# fish-1_0.net
KiCad netlist of a schematic drawn in EAGLE
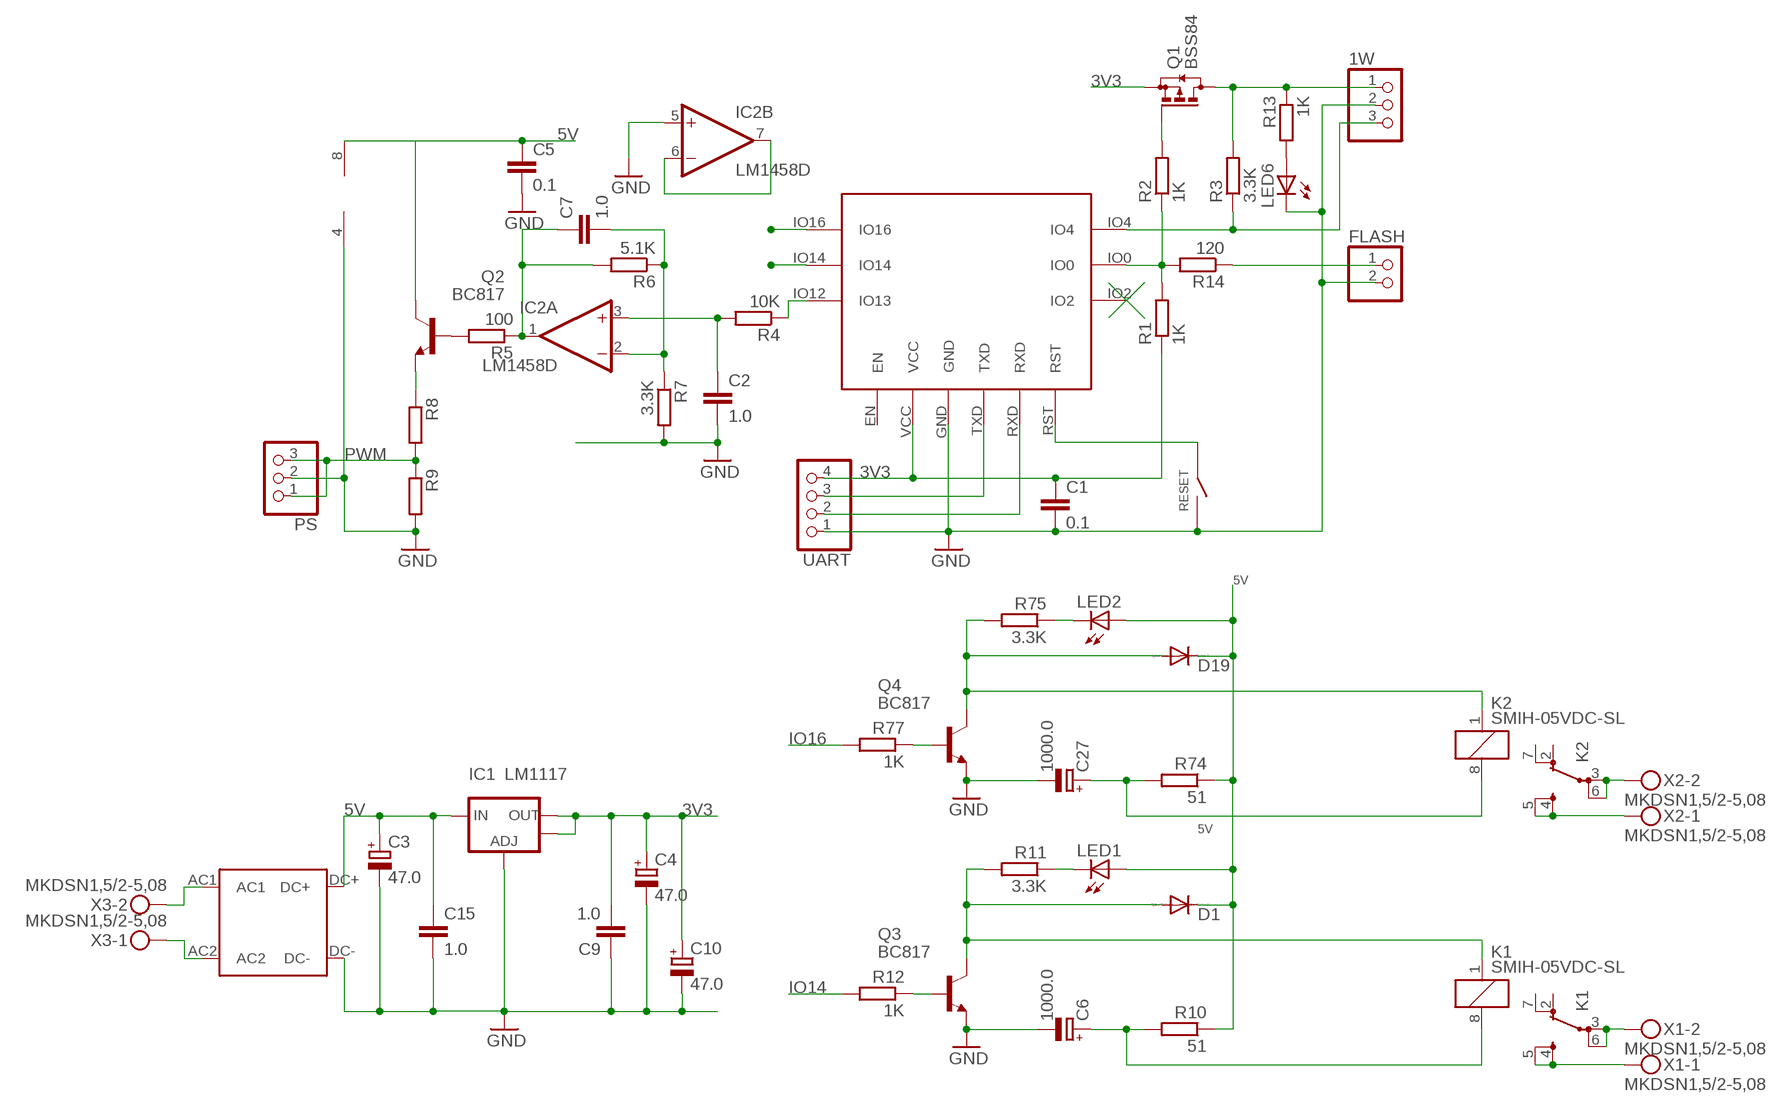
[diagram p0: schematic, sheet 1]

(export (version "E")
  (design (tool "Eeschema 10.0.6"))
  (components
    (comp (ref "1W")
      (value "PINHD-1X3/90")
      (footprint "eagle-import:1X03_90")
      (libsource (lib "eagle-import") (part "PINHD-1X3/90"))
    )
    (comp (ref "C1")
      (value "0.1")
      (footprint "eagle-import:C0805")
      (libsource (lib "eagle-import") (part "C-EUC0805"))
    )
    (comp (ref "C2")
      (value "1.0")
      (footprint "eagle-import:C0805")
      (libsource (lib "eagle-import") (part "C-EUC0805"))
    )
    (comp (ref "C3")
      (value "47.0")
      (footprint "eagle-import:SMC_D")
      (libsource (lib "eagle-import") (part "CPOL-EUSMCD"))
    )
    (comp (ref "C4")
      (value "47.0")
      (footprint "eagle-import:SMC_B")
      (libsource (lib "eagle-import") (part "CPOL-EUSMCB"))
    )
    (comp (ref "C5")
      (value "0.1")
      (footprint "eagle-import:C0805")
      (libsource (lib "eagle-import") (part "C-EUC0805"))
    )
    (comp (ref "C6")
      (value "1000.0")
      (footprint "eagle-import:E3,5-8")
      (libsource (lib "eagle-import") (part "CPOL-EUE3.5-8"))
    )
    (comp (ref "C7")
      (value "1.0")
      (footprint "eagle-import:C0805")
      (libsource (lib "eagle-import") (part "C-EUC0805"))
    )
    (comp (ref "C9")
      (value "1.0")
      (footprint "eagle-import:C0805")
      (libsource (lib "eagle-import") (part "C-EUC0805"))
    )
    (comp (ref "C10")
      (value "47.0")
      (footprint "eagle-import:SMC_D")
      (libsource (lib "eagle-import") (part "CPOL-EUSMCD"))
    )
    (comp (ref "C15")
      (value "1.0")
      (footprint "eagle-import:C0805")
      (libsource (lib "eagle-import") (part "C-EUC0805"))
    )
    (comp (ref "C27")
      (value "1000.0")
      (footprint "eagle-import:E3,5-8")
      (libsource (lib "eagle-import") (part "CPOL-EUE3.5-8"))
    )
    (comp (ref "D1")
      (value "DIODE-SOD123")
      (footprint "eagle-import:SOD123")
      (libsource (lib "eagle-import") (part "DIODE-SOD123"))
    )
    (comp (ref "D19")
      (value "DIODE-SOD123")
      (footprint "eagle-import:SOD123")
      (libsource (lib "eagle-import") (part "DIODE-SOD123"))
    )
    (comp (ref "ESP-M3")
      (value "ESP-M3")
      (footprint "eagle-import:ESP-M3")
      (libsource (lib "eagle-import") (part "ESP-M3"))
    )
    (comp (ref "FLASH")
      (value "PINHD-1X2/90")
      (footprint "eagle-import:1X02_90")
      (libsource (lib "eagle-import") (part "PINHD-1X2/90"))
    )
    (comp (ref "IC1")
      (value "LM1117")
      (footprint "eagle-import:SOT223")
      (libsource (lib "eagle-import") (part "V_REG_LM1117SOT223"))
    )
    (comp (ref "IC2")
      (value "LM1458D")
      (footprint "eagle-import:SO08")
      (libsource (lib "eagle-import") (part "1458DLM"))
    )
    (comp (ref "K1")
      (value "SMIH-05VDC-SL")
      (footprint "eagle-import:FTR-K1C")
      (libsource (lib "eagle-import") (part "FTR-K1C"))
    )
    (comp (ref "K2")
      (value "SMIH-05VDC-SL")
      (footprint "eagle-import:FTR-K1C")
      (libsource (lib "eagle-import") (part "FTR-K1C"))
    )
    (comp (ref "LED1")
      (value "LEDSMT1206")
      (footprint "eagle-import:1206")
      (libsource (lib "eagle-import") (part "LEDSMT1206"))
    )
    (comp (ref "LED2")
      (value "LEDSMT1206")
      (footprint "eagle-import:1206")
      (libsource (lib "eagle-import") (part "LEDSMT1206"))
    )
    (comp (ref "LED6")
      (value "LEDSMT1206")
      (footprint "eagle-import:1206")
      (libsource (lib "eagle-import") (part "LEDSMT1206"))
    )
    (comp (ref "PS")
      (value "PINHD-1X3/90")
      (footprint "eagle-import:1X03_90")
      (libsource (lib "eagle-import") (part "PINHD-1X3/90"))
    )
    (comp (ref "Q1")
      (value "BSS84")
      (footprint "eagle-import:SOT23")
      (libsource (lib "eagle-import") (part "BSS84"))
    )
    (comp (ref "Q2")
      (value "BC817")
      (footprint "eagle-import:SOT23-BEC")
      (libsource (lib "eagle-import") (part "BC817SMD-40"))
    )
    (comp (ref "Q3")
      (value "BC817")
      (footprint "eagle-import:SOT23-BEC")
      (libsource (lib "eagle-import") (part "BC817SMD-40"))
    )
    (comp (ref "Q4")
      (value "BC817")
      (footprint "eagle-import:SOT23-BEC")
      (libsource (lib "eagle-import") (part "BC817SMD-40"))
    )
    (comp (ref "R1")
      (value "1K")
      (footprint "eagle-import:R0603")
      (libsource (lib "eagle-import") (part "R-EU_R0603"))
    )
    (comp (ref "R2")
      (value "1K")
      (footprint "eagle-import:R0603")
      (libsource (lib "eagle-import") (part "R-EU_R0603"))
    )
    (comp (ref "R3")
      (value "3.3K")
      (footprint "eagle-import:R0603")
      (libsource (lib "eagle-import") (part "R-EU_R0603"))
    )
    (comp (ref "R4")
      (value "10K")
      (footprint "eagle-import:R0603")
      (libsource (lib "eagle-import") (part "R-EU_R0603"))
    )
    (comp (ref "R5")
      (value "100")
      (footprint "eagle-import:R0603")
      (libsource (lib "eagle-import") (part "R-EU_R0603"))
    )
    (comp (ref "R6")
      (value "5.1K")
      (footprint "eagle-import:R0603")
      (libsource (lib "eagle-import") (part "R-EU_R0603"))
    )
    (comp (ref "R7")
      (value "3.3K")
      (footprint "eagle-import:R0603")
      (libsource (lib "eagle-import") (part "R-EU_R0603"))
    )
    (comp (ref "R8")
      (value "R-EU_R0603")
      (footprint "eagle-import:R0603")
      (libsource (lib "eagle-import") (part "R-EU_R0603"))
    )
    (comp (ref "R9")
      (value "R-EU_R0603")
      (footprint "eagle-import:R0603")
      (libsource (lib "eagle-import") (part "R-EU_R0603"))
    )
    (comp (ref "R10")
      (value "51")
      (footprint "eagle-import:R1206")
      (libsource (lib "eagle-import") (part "R-EU_R1206"))
    )
    (comp (ref "R11")
      (value "3.3K")
      (footprint "eagle-import:R0603")
      (libsource (lib "eagle-import") (part "R-EU_R0603"))
    )
    (comp (ref "R12")
      (value "1K")
      (footprint "eagle-import:R0603")
      (libsource (lib "eagle-import") (part "R-EU_R0603"))
    )
    (comp (ref "R13")
      (value "1K")
      (footprint "eagle-import:R0603")
      (libsource (lib "eagle-import") (part "R-EU_R0603"))
    )
    (comp (ref "R14")
      (value "120")
      (footprint "eagle-import:R0603")
      (libsource (lib "eagle-import") (part "R-EU_R0603"))
    )
    (comp (ref "R74")
      (value "51")
      (footprint "eagle-import:R1206")
      (libsource (lib "eagle-import") (part "R-EU_R1206"))
    )
    (comp (ref "R75")
      (value "3.3K")
      (footprint "eagle-import:R0603")
      (libsource (lib "eagle-import") (part "R-EU_R0603"))
    )
    (comp (ref "R77")
      (value "1K")
      (footprint "eagle-import:R0603")
      (libsource (lib "eagle-import") (part "R-EU_R0603"))
    )
    (comp (ref "RESET")
      (value "TACT3X4")
      (footprint "eagle-import:TACT3X4")
      (libsource (lib "eagle-import") (part "TACT3X4"))
    )
    (comp (ref "U$1")
      (value "AC-DC/10W-12V")
      (footprint "eagle-import:AC-DC_10W")
      (libsource (lib "eagle-import") (part "AC-DC/10W-12V"))
    )
    (comp (ref "UART")
      (value "PINHD-1X4/90")
      (footprint "eagle-import:1X04_90")
      (libsource (lib "eagle-import") (part "PINHD-1X4/90"))
    )
    (comp (ref "X1")
      (value "MKDSN1,5/2-5,08")
      (footprint "eagle-import:MKDSN1,5_2-5,08")
      (libsource (lib "eagle-import") (part "MKDSN1,5/2-5,08"))
    )
    (comp (ref "X2")
      (value "MKDSN1,5/2-5,08")
      (footprint "eagle-import:MKDSN1,5_2-5,08")
      (libsource (lib "eagle-import") (part "MKDSN1,5/2-5,08"))
    )
    (comp (ref "X3")
      (value "MKDSN1,5/2-5,08")
      (footprint "eagle-import:MKDSN1,5_2-5,08")
      (libsource (lib "eagle-import") (part "MKDSN1,5/2-5,08"))
    )
  )
  (nets
    (net (code "1") (name "/3V3") (class "Default")
      (node (ref "C1") (pin "1") (pinfunction "1_1") (pintype "passive"))
      (node (ref "C10") (pin "+") (pinfunction "+_+") (pintype "passive"))
      (node (ref "C4") (pin "+") (pinfunction "+_+") (pintype "passive"))
      (node (ref "C9") (pin "2") (pinfunction "2_2") (pintype "passive"))
      (node (ref "ESP-M3") (pin "VCC") (pinfunction "VCC_VCC") (pintype "bidirectional"))
      (node (ref "IC1") (pin "2") (pinfunction "OUT_2") (pintype "output"))
      (node (ref "IC1") (pin "4") (pinfunction "OUT_4") (pintype "output"))
      (node (ref "Q1") (pin "2") (pinfunction "S_2") (pintype "passive"))
      (node (ref "R1") (pin "1") (pinfunction "1_1") (pintype "passive"))
      (node (ref "UART") (pin "4") (pinfunction "4_4") (pintype "passive"))
    )
    (net (code "2") (name "/5V") (class "Default")
      (node (ref "C15") (pin "1") (pinfunction "1_1") (pintype "passive"))
      (node (ref "C3") (pin "+") (pinfunction "+_+") (pintype "passive"))
      (node (ref "C5") (pin "1") (pinfunction "1_1") (pintype "passive"))
      (node (ref "D1") (pin "C") (pinfunction "C_C") (pintype "passive"))
      (node (ref "D19") (pin "C") (pinfunction "C_C") (pintype "passive"))
      (node (ref "IC1") (pin "3") (pinfunction "IN_3") (pintype "input"))
      (node (ref "IC2") (pin "8") (pinfunction "V+_8") (pintype "power_in"))
      (node (ref "LED1") (pin "A") (pinfunction "A_A") (pintype "passive"))
      (node (ref "LED2") (pin "A") (pinfunction "A_A") (pintype "passive"))
      (node (ref "Q2") (pin "C") (pinfunction "C_C") (pintype "passive"))
      (node (ref "R10") (pin "1") (pinfunction "1_1") (pintype "passive"))
      (node (ref "R74") (pin "1") (pinfunction "1_1") (pintype "passive"))
      (node (ref "U$1") (pin "DC+") (pinfunction "DC+_DC+") (pintype "power_in"))
    )
    (net (code "3") (name "/IO14") (class "Default")
      (node (ref "ESP-M3") (pin "IO14") (pinfunction "IO14_IO14") (pintype "bidirectional"))
      (node (ref "R12") (pin "2") (pinfunction "2_2") (pintype "passive"))
    )
    (net (code "4") (name "/IO16") (class "Default")
      (node (ref "ESP-M3") (pin "IO16") (pinfunction "IO16_IO16") (pintype "bidirectional"))
      (node (ref "R77") (pin "2") (pinfunction "2_2") (pintype "passive"))
    )
    (net (code "5") (name "/PWM") (class "Default")
      (node (ref "PS") (pin "1") (pinfunction "1_1") (pintype "passive"))
      (node (ref "PS") (pin "3") (pinfunction "3_3") (pintype "passive"))
      (node (ref "R8") (pin "2") (pinfunction "2_2") (pintype "passive"))
      (node (ref "R9") (pin "1") (pinfunction "1_1") (pintype "passive"))
    )
    (net (code "6") (name "GND") (class "Default")
      (node (ref "1W") (pin "2") (pinfunction "2_2") (pintype "passive"))
      (node (ref "C1") (pin "2") (pinfunction "2_2") (pintype "passive"))
      (node (ref "C10") (pin "-") (pinfunction "-_-") (pintype "passive"))
      (node (ref "C15") (pin "2") (pinfunction "2_2") (pintype "passive"))
      (node (ref "C2") (pin "2") (pinfunction "2_2") (pintype "passive"))
      (node (ref "C27") (pin "-") (pinfunction "-_-") (pintype "passive"))
      (node (ref "C3") (pin "-") (pinfunction "-_-") (pintype "passive"))
      (node (ref "C4") (pin "-") (pinfunction "-_-") (pintype "passive"))
      (node (ref "C5") (pin "2") (pinfunction "2_2") (pintype "passive"))
      (node (ref "C6") (pin "-") (pinfunction "-_-") (pintype "passive"))
      (node (ref "C9") (pin "1") (pinfunction "1_1") (pintype "passive"))
      (node (ref "ESP-M3") (pin "GND") (pinfunction "GND_GND") (pintype "bidirectional"))
      (node (ref "FLASH") (pin "2") (pinfunction "2_2") (pintype "passive"))
      (node (ref "IC1") (pin "1") (pinfunction "ADJ_1") (pintype "input"))
      (node (ref "IC2") (pin "4") (pinfunction "V-_4") (pintype "power_in"))
      (node (ref "IC2") (pin "5") (pinfunction "+IN_5") (pintype "input"))
      (node (ref "LED6") (pin "C") (pinfunction "C_C") (pintype "passive"))
      (node (ref "PS") (pin "2") (pinfunction "2_2") (pintype "passive"))
      (node (ref "Q3") (pin "E") (pinfunction "E_E") (pintype "passive"))
      (node (ref "Q4") (pin "E") (pinfunction "E_E") (pintype "passive"))
      (node (ref "R7") (pin "2") (pinfunction "2_2") (pintype "passive"))
      (node (ref "R9") (pin "2") (pinfunction "2_2") (pintype "passive"))
      (node (ref "RESET") (pin "P$2") (pinfunction "P$2_P$2") (pintype "bidirectional"))
      (node (ref "U$1") (pin "DC-") (pinfunction "DC-_DC-") (pintype "power_in"))
      (node (ref "UART") (pin "1") (pinfunction "1_1") (pintype "passive"))
    )
    (net (code "7") (name "Net-(1W-Pad3)") (class "Default")
      (node (ref "1W") (pin "3") (pinfunction "3_3") (pintype "passive"))
      (node (ref "ESP-M3") (pin "IO4") (pinfunction "IO4_IO4") (pintype "bidirectional"))
      (node (ref "R3") (pin "1") (pinfunction "1_1") (pintype "passive"))
    )
    (net (code "8") (name "Net-(D1-PadA)") (class "Default")
      (node (ref "D1") (pin "A") (pinfunction "A_A") (pintype "passive"))
      (node (ref "K1") (pin "1") (pinfunction "1_1") (pintype "passive"))
      (node (ref "Q3") (pin "C") (pinfunction "C_C") (pintype "passive"))
      (node (ref "R11") (pin "2") (pinfunction "2_2") (pintype "passive"))
    )
    (net (code "9") (name "Net-(D19-PadA)") (class "Default")
      (node (ref "D19") (pin "A") (pinfunction "A_A") (pintype "passive"))
      (node (ref "K2") (pin "1") (pinfunction "1_1") (pintype "passive"))
      (node (ref "Q4") (pin "C") (pinfunction "C_C") (pintype "passive"))
      (node (ref "R75") (pin "2") (pinfunction "2_2") (pintype "passive"))
    )
    (net (code "10") (name "Net-(ESP-M3-IO13)") (class "Default")
      (node (ref "ESP-M3") (pin "IO12") (pinfunction "IO13_IO12") (pintype "bidirectional"))
      (node (ref "R4") (pin "1") (pinfunction "1_1") (pintype "passive"))
    )
    (net (code "11") (name "Net-(ESP-M3-PadIO0)") (class "Default")
      (node (ref "ESP-M3") (pin "IO0") (pinfunction "IO0_IO0") (pintype "bidirectional"))
      (node (ref "R1") (pin "2") (pinfunction "2_2") (pintype "passive"))
      (node (ref "R14") (pin "2") (pinfunction "2_2") (pintype "passive"))
      (node (ref "R2") (pin "1") (pinfunction "1_1") (pintype "passive"))
    )
    (net (code "12") (name "Net-(ESP-M3-PadRST)") (class "Default")
      (node (ref "ESP-M3") (pin "RST") (pinfunction "RST_RST") (pintype "bidirectional"))
      (node (ref "RESET") (pin "P$1") (pinfunction "P$1_P$1") (pintype "bidirectional"))
    )
    (net (code "13") (name "Net-(ESP-M3-PadRXD)") (class "Default")
      (node (ref "ESP-M3") (pin "RXD") (pinfunction "RXD_RXD") (pintype "bidirectional"))
      (node (ref "UART") (pin "2") (pinfunction "2_2") (pintype "passive"))
    )
    (net (code "14") (name "Net-(ESP-M3-PadTXD)") (class "Default")
      (node (ref "ESP-M3") (pin "TXD") (pinfunction "TXD_TXD") (pintype "bidirectional"))
      (node (ref "UART") (pin "3") (pinfunction "3_3") (pintype "passive"))
    )
    (net (code "15") (name "Net-(FLASH-Pad1)") (class "Default")
      (node (ref "FLASH") (pin "1") (pinfunction "1_1") (pintype "passive"))
      (node (ref "R14") (pin "1") (pinfunction "1_1") (pintype "passive"))
    )
    (net (code "16") (name "Net-(IC2A-+IN)") (class "Default")
      (node (ref "C2") (pin "1") (pinfunction "1_1") (pintype "passive"))
      (node (ref "IC2") (pin "3") (pinfunction "+IN_3") (pintype "input"))
      (node (ref "R4") (pin "2") (pinfunction "2_2") (pintype "passive"))
    )
    (net (code "17") (name "Net-(IC2A--IN)") (class "Default")
      (node (ref "C7") (pin "2") (pinfunction "2_2") (pintype "passive"))
      (node (ref "IC2") (pin "2") (pinfunction "-IN_2") (pintype "input"))
      (node (ref "R6") (pin "1") (pinfunction "1_1") (pintype "passive"))
      (node (ref "R7") (pin "1") (pinfunction "1_1") (pintype "passive"))
    )
    (net (code "18") (name "Net-(IC2A-OUT)") (class "Default")
      (node (ref "C7") (pin "1") (pinfunction "1_1") (pintype "passive"))
      (node (ref "IC2") (pin "1") (pinfunction "OUT_1") (pintype "output"))
      (node (ref "R5") (pin "1") (pinfunction "1_1") (pintype "passive"))
      (node (ref "R6") (pin "2") (pinfunction "2_2") (pintype "passive"))
    )
    (net (code "19") (name "Net-(IC2B--IN)") (class "Default")
      (node (ref "IC2") (pin "6") (pinfunction "-IN_6") (pintype "input"))
      (node (ref "IC2") (pin "7") (pinfunction "OUT_7") (pintype "output"))
    )
    (net (code "20") (name "Net-(K1A-PA)") (class "Default")
      (node (ref "K1") (pin "3") (pinfunction "PA_3") (pintype "passive"))
      (node (ref "K1") (pin "6") (pinfunction "PB_6") (pintype "passive"))
      (node (ref "X1") (pin "2") (pinfunction "KL_2") (pintype "passive"))
    )
    (net (code "21") (name "Net-(K1A-SA)") (class "Default")
      (node (ref "K1") (pin "4") (pinfunction "SA_4") (pintype "passive"))
      (node (ref "K1") (pin "5") (pinfunction "SB_5") (pintype "passive"))
      (node (ref "X1") (pin "1") (pinfunction "KL_1") (pintype "passive"))
    )
    (net (code "22") (name "Net-(K1B-2)") (class "Default")
      (node (ref "C6") (pin "+") (pinfunction "+_+") (pintype "passive"))
      (node (ref "K1") (pin "8") (pinfunction "2_8") (pintype "passive"))
      (node (ref "R10") (pin "2") (pinfunction "2_2") (pintype "passive"))
    )
    (net (code "23") (name "Net-(K2A-PA)") (class "Default")
      (node (ref "K2") (pin "3") (pinfunction "PA_3") (pintype "passive"))
      (node (ref "K2") (pin "6") (pinfunction "PB_6") (pintype "passive"))
      (node (ref "X2") (pin "2") (pinfunction "KL_2") (pintype "passive"))
    )
    (net (code "24") (name "Net-(K2A-SA)") (class "Default")
      (node (ref "K2") (pin "4") (pinfunction "SA_4") (pintype "passive"))
      (node (ref "K2") (pin "5") (pinfunction "SB_5") (pintype "passive"))
      (node (ref "X2") (pin "1") (pinfunction "KL_1") (pintype "passive"))
    )
    (net (code "25") (name "Net-(K2B-2)") (class "Default")
      (node (ref "C27") (pin "+") (pinfunction "+_+") (pintype "passive"))
      (node (ref "K2") (pin "8") (pinfunction "2_8") (pintype "passive"))
      (node (ref "R74") (pin "2") (pinfunction "2_2") (pintype "passive"))
    )
    (net (code "26") (name "Net-(LED1-PadC)") (class "Default")
      (node (ref "LED1") (pin "C") (pinfunction "C_C") (pintype "passive"))
      (node (ref "R11") (pin "1") (pinfunction "1_1") (pintype "passive"))
    )
    (net (code "27") (name "Net-(LED2-PadC)") (class "Default")
      (node (ref "LED2") (pin "C") (pinfunction "C_C") (pintype "passive"))
      (node (ref "R75") (pin "1") (pinfunction "1_1") (pintype "passive"))
    )
    (net (code "28") (name "Net-(LED6-PadA)") (class "Default")
      (node (ref "LED6") (pin "A") (pinfunction "A_A") (pintype "passive"))
      (node (ref "R13") (pin "2") (pinfunction "2_2") (pintype "passive"))
    )
    (net (code "29") (name "Net-(Q1-D)") (class "Default")
      (node (ref "1W") (pin "1") (pinfunction "1_1") (pintype "passive"))
      (node (ref "Q1") (pin "3") (pinfunction "D_3") (pintype "passive"))
      (node (ref "R13") (pin "1") (pinfunction "1_1") (pintype "passive"))
      (node (ref "R3") (pin "2") (pinfunction "2_2") (pintype "passive"))
    )
    (net (code "30") (name "Net-(Q1-G)") (class "Default")
      (node (ref "Q1") (pin "1") (pinfunction "G_1") (pintype "passive"))
      (node (ref "R2") (pin "2") (pinfunction "2_2") (pintype "passive"))
    )
    (net (code "31") (name "Net-(Q2-PadB)") (class "Default")
      (node (ref "Q2") (pin "B") (pinfunction "B_B") (pintype "passive"))
      (node (ref "R5") (pin "2") (pinfunction "2_2") (pintype "passive"))
    )
    (net (code "32") (name "Net-(Q2-PadE)") (class "Default")
      (node (ref "Q2") (pin "E") (pinfunction "E_E") (pintype "passive"))
      (node (ref "R8") (pin "1") (pinfunction "1_1") (pintype "passive"))
    )
    (net (code "33") (name "Net-(Q3-PadB)") (class "Default")
      (node (ref "Q3") (pin "B") (pinfunction "B_B") (pintype "passive"))
      (node (ref "R12") (pin "1") (pinfunction "1_1") (pintype "passive"))
    )
    (net (code "34") (name "Net-(Q4-PadB)") (class "Default")
      (node (ref "Q4") (pin "B") (pinfunction "B_B") (pintype "passive"))
      (node (ref "R77") (pin "1") (pinfunction "1_1") (pintype "passive"))
    )
    (net (code "35") (name "Net-(X3A-KL)") (class "Default")
      (node (ref "U$1") (pin "AC2") (pinfunction "AC2_AC2") (pintype "power_in"))
      (node (ref "X3") (pin "1") (pinfunction "KL_1") (pintype "passive"))
    )
    (net (code "36") (name "Net-(X3B-KL)") (class "Default")
      (node (ref "U$1") (pin "AC1") (pinfunction "AC1_AC1") (pintype "power_in"))
      (node (ref "X3") (pin "2") (pinfunction "KL_2") (pintype "passive"))
    )
    (net (code "37") (name "unconnected-(ESP-M3-PadEN)") (class "Default")
      (node (ref "ESP-M3") (pin "EN") (pinfunction "EN_EN") (pintype "bidirectional"))
    )
    (net (code "38") (name "unconnected-(ESP-M3-PadIO2)") (class "Default")
      (node (ref "ESP-M3") (pin "IO2") (pinfunction "IO2_IO2") (pintype "bidirectional"))
    )
    (net (code "39") (name "unconnected-(K1A-OA-Pad2)") (class "Default")
      (node (ref "K1") (pin "2") (pinfunction "OA_2") (pintype "passive"))
    )
    (net (code "40") (name "unconnected-(K1A-OB-Pad7)") (class "Default")
      (node (ref "K1") (pin "7") (pinfunction "OB_7") (pintype "passive"))
    )
    (net (code "41") (name "unconnected-(K2A-OA-Pad2)") (class "Default")
      (node (ref "K2") (pin "2") (pinfunction "OA_2") (pintype "passive"))
    )
    (net (code "42") (name "unconnected-(K2A-OB-Pad7)") (class "Default")
      (node (ref "K2") (pin "7") (pinfunction "OB_7") (pintype "passive"))
    )
  )
)
